# AugmentedStethoscope_vFinal.net
KiCad netlist of a schematic drawn in EAGLE
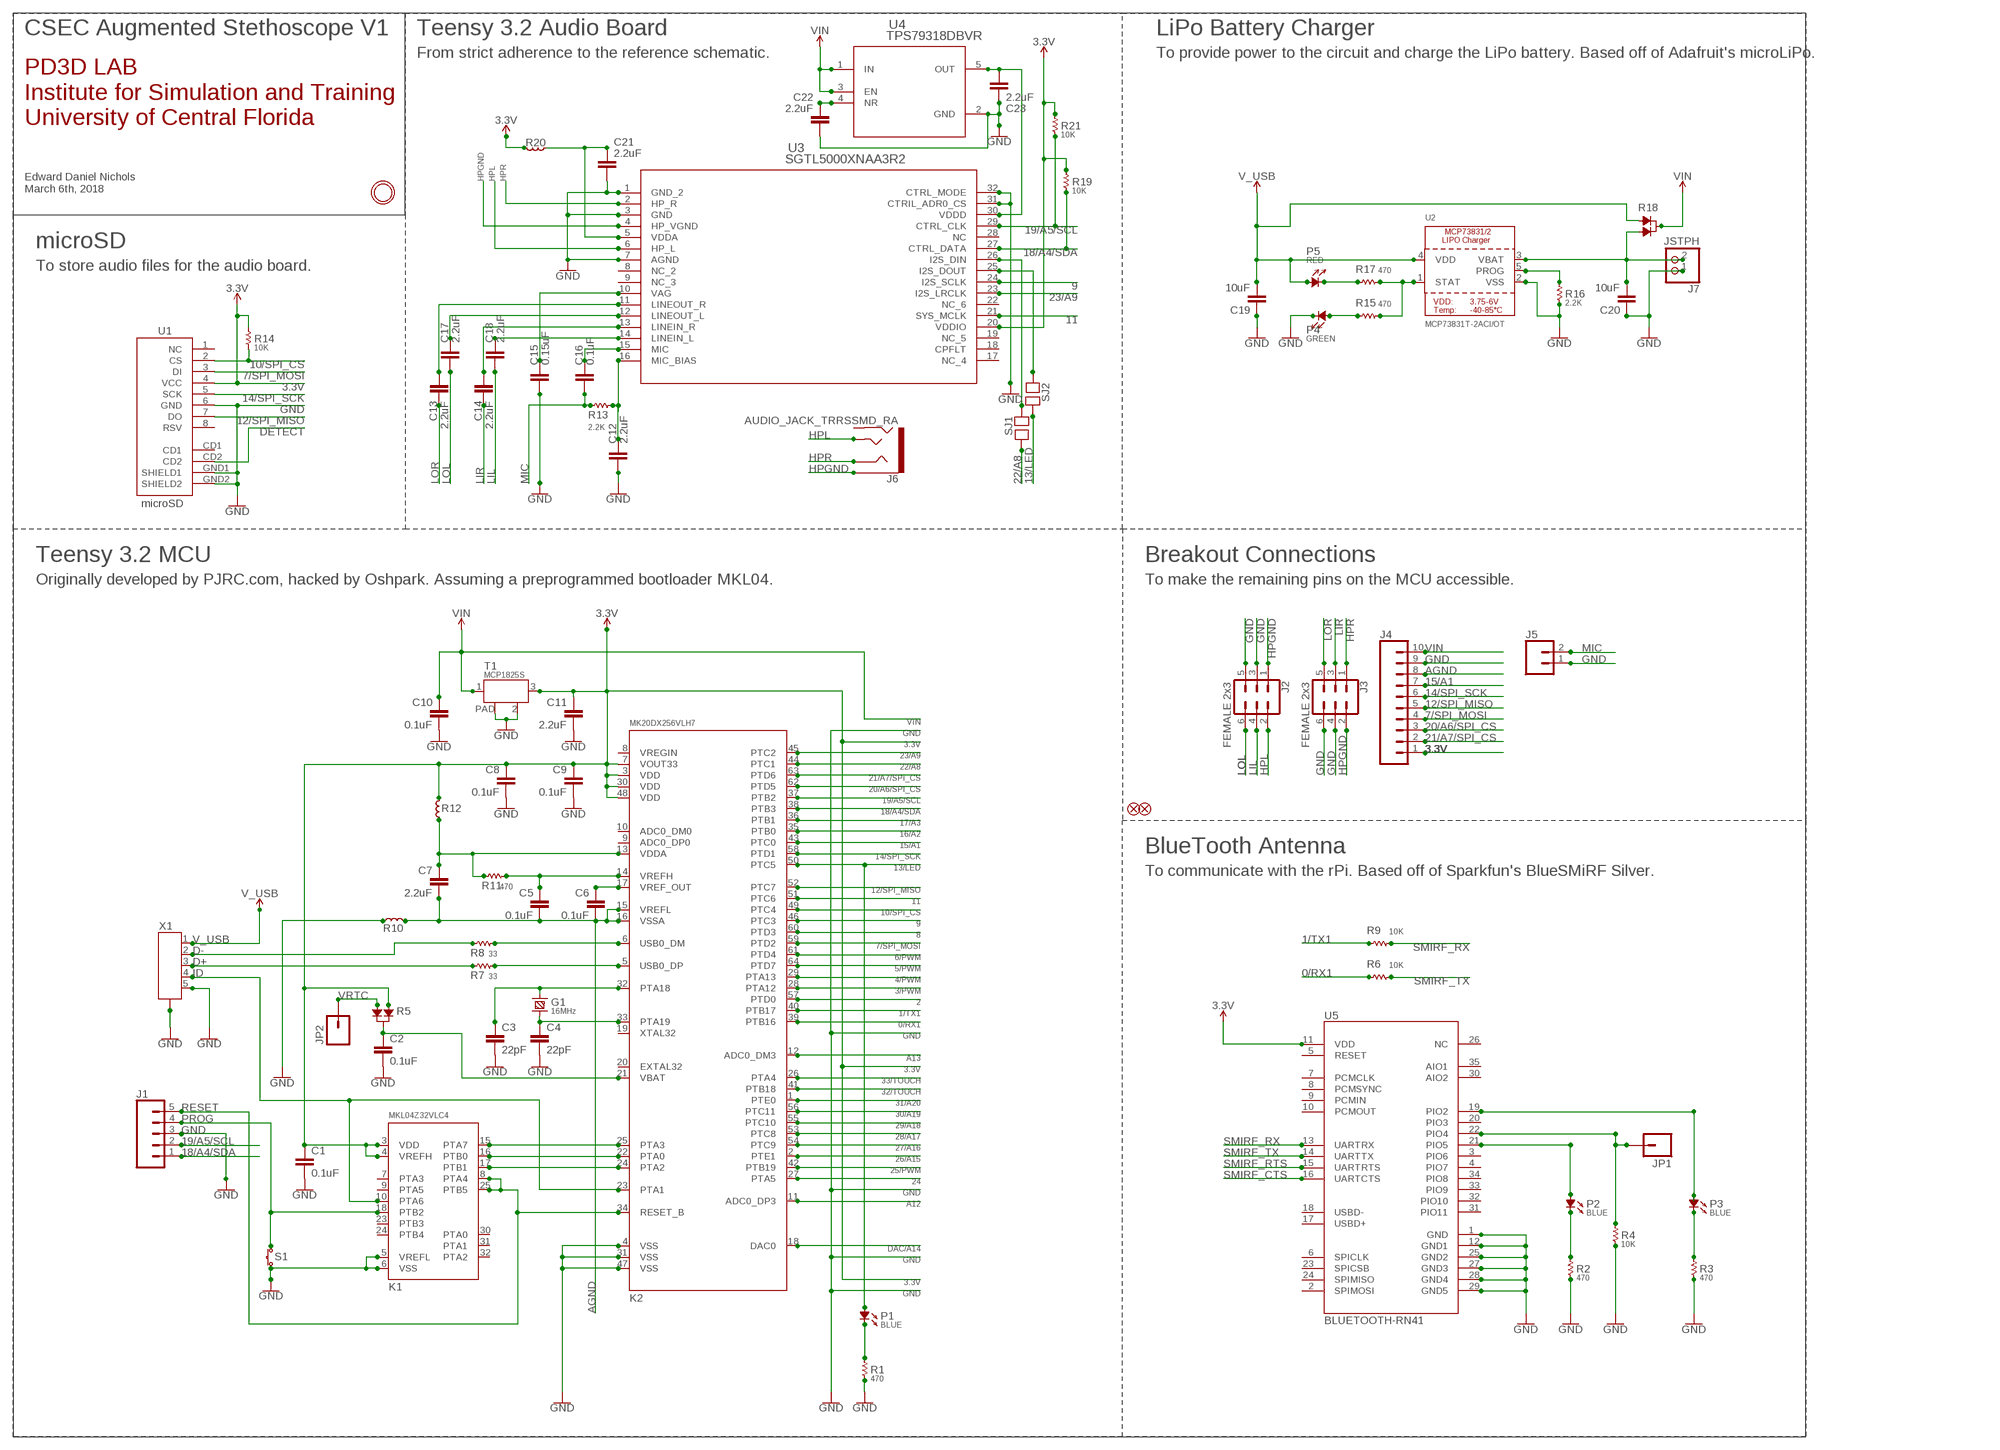
[diagram p0: schematic, sheet 1]

(export (version "E")
  (design (tool "Eeschema 10.0.6"))
  (components
    (comp (ref "C1")
      (value "0.1uF")
      (footprint "eagle-import:0603")
      (libsource (lib "eagle-import") (part "0.1UF-0603-25V-5%"))
    )
    (comp (ref "C2")
      (value "0.1uF")
      (footprint "eagle-import:0603")
      (libsource (lib "eagle-import") (part "0.1UF-0603-25V-5%"))
    )
    (comp (ref "C3")
      (value "22pF")
      (footprint "eagle-import:0603")
      (libsource (lib "eagle-import") (part "22PF-0603-50V-5%"))
    )
    (comp (ref "C4")
      (value "22pF")
      (footprint "eagle-import:0603")
      (libsource (lib "eagle-import") (part "22PF-0603-50V-5%"))
    )
    (comp (ref "C5")
      (value "0.1uF")
      (footprint "eagle-import:0603")
      (libsource (lib "eagle-import") (part "0.1UF-0603-25V-5%"))
    )
    (comp (ref "C6")
      (value "0.1uF")
      (footprint "eagle-import:0603")
      (libsource (lib "eagle-import") (part "0.1UF-0603-25V-5%"))
    )
    (comp (ref "C7")
      (value "2.2uF")
      (footprint "eagle-import:0603")
      (libsource (lib "eagle-import") (part "2.2UF-0603-10V-20%"))
    )
    (comp (ref "C8")
      (value "0.1uF")
      (footprint "eagle-import:0603")
      (libsource (lib "eagle-import") (part "0.1UF-0603-25V-5%"))
    )
    (comp (ref "C9")
      (value "0.1uF")
      (footprint "eagle-import:0603")
      (libsource (lib "eagle-import") (part "0.1UF-0603-25V-5%"))
    )
    (comp (ref "C10")
      (value "0.1uF")
      (footprint "eagle-import:0603")
      (libsource (lib "eagle-import") (part "0.1UF-0603-25V-5%"))
    )
    (comp (ref "C11")
      (value "2.2uF")
      (footprint "eagle-import:0603")
      (libsource (lib "eagle-import") (part "2.2UF-0603-10V-20%"))
    )
    (comp (ref "C12")
      (value "2.2uF")
      (footprint "eagle-import:0603")
      (libsource (lib "eagle-import") (part "2.2UF-0603-10V-20%"))
    )
    (comp (ref "C13")
      (value "2.2uF")
      (footprint "eagle-import:0603")
      (libsource (lib "eagle-import") (part "2.2UF-0603-10V-20%"))
    )
    (comp (ref "C14")
      (value "2.2uF")
      (footprint "eagle-import:0603")
      (libsource (lib "eagle-import") (part "2.2UF-0603-10V-20%"))
    )
    (comp (ref "C15")
      (value "0.15uF")
      (footprint "eagle-import:0603")
      (libsource (lib "eagle-import") (part "0.1UF-0603-25V-5%"))
    )
    (comp (ref "C16")
      (value "0.1uF")
      (footprint "eagle-import:0603")
      (libsource (lib "eagle-import") (part "0.1UF-0603-25V-5%"))
    )
    (comp (ref "C17")
      (value "2.2uF")
      (footprint "eagle-import:0603")
      (libsource (lib "eagle-import") (part "2.2UF-0603-10V-20%"))
    )
    (comp (ref "C18")
      (value "2.2uF")
      (footprint "eagle-import:0603")
      (libsource (lib "eagle-import") (part "2.2UF-0603-10V-20%"))
    )
    (comp (ref "C19")
      (value "10uF")
      (footprint "eagle-import:0805")
      (libsource (lib "eagle-import") (part "10UF-0805-10V-10%"))
    )
    (comp (ref "C20")
      (value "10uF")
      (footprint "eagle-import:0805")
      (libsource (lib "eagle-import") (part "10UF-0805-10V-10%"))
    )
    (comp (ref "C21")
      (value "2.2uF")
      (footprint "eagle-import:0603")
      (libsource (lib "eagle-import") (part "2.2UF-0603-10V-20%"))
    )
    (comp (ref "C22")
      (value "2.2uF")
      (footprint "eagle-import:0603")
      (libsource (lib "eagle-import") (part "2.2UF-0603-10V-20%"))
    )
    (comp (ref "C23")
      (value "2.2uF")
      (footprint "eagle-import:0603")
      (libsource (lib "eagle-import") (part "2.2UF-0603-10V-20%"))
    )
    (comp (ref "FID1")
      (value "FIDUCIAL\"\"")
      (footprint "eagle-import:FIDUCIAL_1MM")
      (fields (field (name "BOM") "EXCLUDE"))
      (libsource (lib "eagle-import") (part "FIDUCIAL{dblquote}{dblquote}"))
    )
    (comp (ref "FID2")
      (value "FIDUCIAL\"\"")
      (footprint "eagle-import:FIDUCIAL_1MM")
      (libsource (lib "eagle-import") (part "FIDUCIAL{dblquote}{dblquote}"))
    )
    (comp (ref "G1")
      (value "16MHz")
      (footprint "eagle-import:HC49US")
      (fields (field (name "MF") "ABRACON") (field (name "MPN") "ABL-16.000MHz-B1U"))
      (libsource (lib "eagle-import") (part "CRYSTAL-HC49US"))
    )
    (comp (ref "J1")
      (value "CONN_05")
      (footprint "eagle-import:1X05")
      (libsource (lib "eagle-import") (part "CONN_05"))
    )
    (comp (ref "J2")
      (value "FEMALE 2x3")
      (footprint "eagle-import:2X3")
      (libsource (lib "eagle-import") (part "CONN_03X2FEMALE"))
    )
    (comp (ref "J3")
      (value "FEMALE 2x3")
      (footprint "eagle-import:2X3")
      (libsource (lib "eagle-import") (part "CONN_03X2FEMALE"))
    )
    (comp (ref "J4")
      (value "CONN_10\"")
      (footprint "eagle-import:1X10")
      (libsource (lib "eagle-import") (part "CONN_10{dblquote}"))
    )
    (comp (ref "J5")
      (value "CONN_02")
      (footprint "eagle-import:1X02")
      (libsource (lib "eagle-import") (part "CONN_02"))
    )
    (comp (ref "J6")
      (value "AUDIO_JACK_TRRSSMD_RA")
      (footprint "eagle-import:AUDIO_JACK_3.5MM_TRRS_SMD_RA")
      (libsource (lib "eagle-import") (part "AUDIO_JACK_TRRSSMD_RA"))
    )
    (comp (ref "J7")
      (value "JSTPH")
      (footprint "eagle-import:JSTPH2")
      (libsource (lib "eagle-import") (part "JST_2PIN"))
    )
    (comp (ref "JP1")
      (value "M01SMDNS")
      (footprint "eagle-import:1X01NS")
      (libsource (lib "eagle-import") (part "M01SMDNS"))
    )
    (comp (ref "JP2")
      (value "M01SMDNS")
      (footprint "eagle-import:1X01NS")
      (libsource (lib "eagle-import") (part "M01SMDNS"))
    )
    (comp (ref "K1")
      (value "MKL04Z32VLC4")
      (footprint "eagle-import:LQFP32-08")
      (fields (field (name "MF") "PJRC") (field (name "MPN") "IC_MKL04Z32_TQFP32"))
      (libsource (lib "eagle-import") (part "MKL04Z32VLC4"))
    )
    (comp (ref "K2")
      (value "MK20DX256VLH7")
      (footprint "eagle-import:LQFP64-05")
      (fields (field (name "MF") "NXP"))
      (libsource (lib "eagle-import") (part "MK20DX256VLH7"))
    )
    (comp (ref "P1")
      (value "BLUE")
      (footprint "eagle-import:LED-0805")
      (fields (field (name "MF") "ROHM Semiconductor") (field (name "MPN") "SML-211DTT86"))
      (libsource (lib "eagle-import") (part "LED"))
    )
    (comp (ref "P2")
      (value "BLUE")
      (footprint "eagle-import:LED-0805")
      (fields (field (name "MF") "ROHM Semiconductor") (field (name "MPN") "SML-211DTT86"))
      (libsource (lib "eagle-import") (part "LED"))
    )
    (comp (ref "P3")
      (value "BLUE")
      (footprint "eagle-import:LED-0805")
      (fields (field (name "MF") "ROHM Semiconductor") (field (name "MPN") "SML-211DTT86"))
      (libsource (lib "eagle-import") (part "LED"))
    )
    (comp (ref "P4")
      (value "GREEN")
      (footprint "eagle-import:LED-0805")
      (fields (field (name "MF") "ROHM Semiconductor") (field (name "MPN") "SML-211DTT86"))
      (libsource (lib "eagle-import") (part "LED"))
    )
    (comp (ref "P5")
      (value "RED")
      (footprint "eagle-import:LED-0805")
      (fields (field (name "MF") "ROHM Semiconductor") (field (name "MPN") "SML-211DTT86"))
      (libsource (lib "eagle-import") (part "LED"))
    )
    (comp (ref "R1")
      (value "470")
      (footprint "eagle-import:R0603")
      (fields (field (name "MF") "Vishay") (field (name "MPN") "CRCW0603470RFKEA"))
      (libsource (lib "eagle-import") (part "RESISTOR-470R"))
    )
    (comp (ref "R2")
      (value "470")
      (footprint "eagle-import:R0603")
      (fields (field (name "MF") "Vishay") (field (name "MPN") "CRCW0603470RFKEA"))
      (libsource (lib "eagle-import") (part "RESISTOR-470R"))
    )
    (comp (ref "R3")
      (value "470")
      (footprint "eagle-import:R0603")
      (fields (field (name "MF") "Vishay") (field (name "MPN") "CRCW0603470RFKEA"))
      (libsource (lib "eagle-import") (part "RESISTOR-470R"))
    )
    (comp (ref "R4")
      (value "10K")
      (footprint "eagle-import:R0603")
      (fields (field (name "MF") "Vishay") (field (name "MPN") "CRCW0603470RFKEA"))
      (libsource (lib "eagle-import") (part "RESISTOR-470R"))
    )
    (comp (ref "R5")
      (value "DIODE_DUAL")
      (footprint "eagle-import:SOT-23")
      (fields (field (name "MF") "NXP Semiconductors") (field (name "MPN") "BAT54C,215"))
      (libsource (lib "eagle-import") (part "DIODE_DUAL"))
    )
    (comp (ref "R6")
      (value "10K")
      (footprint "eagle-import:R0603")
      (fields (field (name "MF") "Panasonic") (field (name "MPN") "ERJ-PA3F33R0V"))
      (libsource (lib "eagle-import") (part "RESISTOR-33R"))
    )
    (comp (ref "R7")
      (value "33")
      (footprint "eagle-import:R0603")
      (fields (field (name "MF") "Panasonic") (field (name "MPN") "ERJ-PA3F33R0V"))
      (libsource (lib "eagle-import") (part "RESISTOR-33R"))
    )
    (comp (ref "R8")
      (value "33")
      (footprint "eagle-import:R0603")
      (fields (field (name "MF") "Panasonic") (field (name "MPN") "ERJ-PA3F33R0V"))
      (libsource (lib "eagle-import") (part "RESISTOR-33R"))
    )
    (comp (ref "R9")
      (value "10K")
      (footprint "eagle-import:R0603")
      (fields (field (name "MF") "Panasonic") (field (name "MPN") "ERJ-PA3F33R0V"))
      (libsource (lib "eagle-import") (part "RESISTOR-33R"))
    )
    (comp (ref "R10")
      (value "FERRITE")
      (footprint "eagle-import:L0603")
      (fields (field (name "MF") "Murata Electronics") (field (name "MPN") " BLM18AG601SN1D"))
      (libsource (lib "eagle-import") (part "FERRITE"))
    )
    (comp (ref "R11")
      (value "470")
      (footprint "eagle-import:R0603")
      (fields (field (name "MF") "Vishay") (field (name "MPN") "CRCW0603470RFKEA"))
      (libsource (lib "eagle-import") (part "RESISTOR-470R"))
    )
    (comp (ref "R12")
      (value "FERRITE")
      (footprint "eagle-import:L0603")
      (fields (field (name "MF") "Murata Electronics") (field (name "MPN") " BLM18AG601SN1D"))
      (libsource (lib "eagle-import") (part "FERRITE"))
    )
    (comp (ref "R13")
      (value "2.2K")
      (footprint "eagle-import:R0603")
      (fields (field (name "MF") "Vishay") (field (name "MPN") "CRCW0603470RFKEA"))
      (libsource (lib "eagle-import") (part "RESISTOR-470R"))
    )
    (comp (ref "R14")
      (value "10K")
      (footprint "eagle-import:R0603")
      (fields (field (name "MF") "Vishay") (field (name "MPN") "CRCW0603470RFKEA"))
      (libsource (lib "eagle-import") (part "RESISTOR-470R"))
    )
    (comp (ref "R15")
      (value "470")
      (footprint "eagle-import:R0603")
      (fields (field (name "MF") "Panasonic") (field (name "MPN") "ERJ-PA3F33R0V"))
      (libsource (lib "eagle-import") (part "RESISTOR-33R"))
    )
    (comp (ref "R16")
      (value "2.2K")
      (footprint "eagle-import:R0603")
      (fields (field (name "MF") "Vishay") (field (name "MPN") "CRCW0603470RFKEA"))
      (libsource (lib "eagle-import") (part "RESISTOR-470R"))
    )
    (comp (ref "R17")
      (value "470")
      (footprint "eagle-import:R0603")
      (fields (field (name "MF") "Panasonic") (field (name "MPN") "ERJ-PA3F33R0V"))
      (libsource (lib "eagle-import") (part "RESISTOR-33R"))
    )
    (comp (ref "R18")
      (value "DIODE_DUAL")
      (footprint "eagle-import:SOT-23")
      (fields (field (name "MF") "NXP Semiconductors") (field (name "MPN") "BAT54C,215"))
      (libsource (lib "eagle-import") (part "DIODE_DUAL"))
    )
    (comp (ref "R19")
      (value "10K")
      (footprint "eagle-import:R0603")
      (fields (field (name "MF") "Vishay") (field (name "MPN") "CRCW0603470RFKEA"))
      (libsource (lib "eagle-import") (part "RESISTOR-470R"))
    )
    (comp (ref "R20")
      (value "FERRITE")
      (footprint "eagle-import:L0603")
      (fields (field (name "MF") "Murata Electronics") (field (name "MPN") " BLM18AG601SN1D"))
      (libsource (lib "eagle-import") (part "FERRITE"))
    )
    (comp (ref "R21")
      (value "10K")
      (footprint "eagle-import:R0603")
      (fields (field (name "MF") "Vishay") (field (name "MPN") "CRCW0603470RFKEA"))
      (libsource (lib "eagle-import") (part "RESISTOR-470R"))
    )
    (comp (ref "S1")
      (value "TACT_SWITCH")
      (footprint "eagle-import:ALPS_SKHH")
      (fields (field (name "MF") "ALPS") (field (name "MPN") "SKHHPKA010"))
      (libsource (lib "eagle-import") (part "TACT_SWITCH"))
    )
    (comp (ref "SJ1")
      (value "SOLDERJUMPER")
      (footprint "eagle-import:SOLDERJUMPER")
      (libsource (lib "eagle-import") (part "SOLDERJUMPER"))
    )
    (comp (ref "SJ2")
      (value "SOLDERJUMPER")
      (footprint "eagle-import:SOLDERJUMPER")
      (libsource (lib "eagle-import") (part "SOLDERJUMPER"))
    )
    (comp (ref "T1")
      (value "MCP1825S")
      (footprint "eagle-import:SOT-223")
      (fields (field (name "MF") "Microchip Technology") (field (name "MPN") "MCP1825S-3302E/DB"))
      (libsource (lib "eagle-import") (part "LDO"))
    )
    (comp (ref "U$1")
      (value "MOUNTINGHOLE2.5")
      (footprint "eagle-import:MOUNTINGHOLE_2.5_PLATED")
      (libsource (lib "eagle-import") (part "MOUNTINGHOLE2.5"))
    )
    (comp (ref "U1")
      (value "microSD")
      (footprint "eagle-import:MICRO-SD-SOCKET-PP")
      (libsource (lib "eagle-import") (part "USD-SOCKETSMD"))
    )
    (comp (ref "U2")
      (value "MCP73831T-2ACI/OT")
      (footprint "eagle-import:SOT23-5")
      (libsource (lib "eagle-import") (part "MCP73831/2"))
    )
    (comp (ref "U3")
      (value "SGTL5000XNAA3R2")
      (footprint "eagle-import:QFN32")
      (libsource (lib "eagle-import") (part "SGTL5000XNAA3R2"))
    )
    (comp (ref "U4")
      (value "TPS79318DBVR")
      (footprint "eagle-import:DBV5")
      (libsource (lib "eagle-import") (part "TPS79318DBVR"))
    )
    (comp (ref "U5")
      (value "BLUETOOTH-RN41")
      (footprint "eagle-import:RN41")
      (libsource (lib "eagle-import") (part "BLUETOOTH-RN41{dblquote}"))
    )
    (comp (ref "X1")
      (value "MINI-USB")
      (footprint "eagle-import:MOLEX_SD-67503-010")
      (fields (field (name "MF") "MOLEX") (field (name "MPN") "0675031020"))
      (libsource (lib "eagle-import") (part "MINI-USBMOLEX_0675031230"))
    )
  )
  (nets
    (net (code "1") (name "/0{slash}RX1") (class "Default")
      (node (ref "K2") (pin "39") (pinfunction "PTB16_39") (pintype "bidirectional"))
      (node (ref "R6") (pin "1") (pinfunction "1_1") (pintype "passive"))
    )
    (net (code "2") (name "/1{slash}TX1") (class "Default")
      (node (ref "K2") (pin "40") (pinfunction "PTB17_40") (pintype "bidirectional"))
      (node (ref "R9") (pin "1") (pinfunction "1_1") (pintype "passive"))
    )
    (net (code "3") (name "/2") (class "Default")
      (node (ref "K2") (pin "57") (pinfunction "PTD0_57") (pintype "bidirectional"))
    )
    (net (code "4") (name "/3{slash}PWM") (class "Default")
      (node (ref "K2") (pin "28") (pinfunction "PTA12_28") (pintype "bidirectional"))
    )
    (net (code "5") (name "/4{slash}PWM") (class "Default")
      (node (ref "K2") (pin "29") (pinfunction "PTA13_29") (pintype "bidirectional"))
    )
    (net (code "6") (name "/5{slash}PWM") (class "Default")
      (node (ref "K2") (pin "64") (pinfunction "PTD7_64") (pintype "bidirectional"))
    )
    (net (code "7") (name "/6{slash}PWM") (class "Default")
      (node (ref "K2") (pin "61") (pinfunction "PTD4_61") (pintype "bidirectional"))
    )
    (net (code "8") (name "/7{slash}SPI_MOSI") (class "Default")
      (node (ref "J4") (pin "4") (pinfunction "4_4") (pintype "passive"))
      (node (ref "K2") (pin "59") (pinfunction "PTD2_59") (pintype "bidirectional"))
      (node (ref "U1") (pin "3") (pinfunction "DI_3") (pintype "bidirectional"))
    )
    (net (code "9") (name "/8") (class "Default")
      (node (ref "K2") (pin "60") (pinfunction "PTD3_60") (pintype "bidirectional"))
    )
    (net (code "10") (name "/9") (class "Default")
      (node (ref "K2") (pin "46") (pinfunction "PTC3_46") (pintype "bidirectional"))
      (node (ref "U3") (pin "24") (pinfunction "I2S_SCLK_24") (pintype "passive"))
    )
    (net (code "11") (name "/10{slash}SPI_CS") (class "Default")
      (node (ref "K2") (pin "49") (pinfunction "PTC4_49") (pintype "bidirectional"))
      (node (ref "R14") (pin "1") (pinfunction "1_1") (pintype "passive"))
      (node (ref "U1") (pin "2") (pinfunction "CS_2") (pintype "bidirectional"))
    )
    (net (code "12") (name "/11") (class "Default")
      (node (ref "K2") (pin "51") (pinfunction "PTC6_51") (pintype "bidirectional"))
      (node (ref "U3") (pin "21") (pinfunction "SYS_MCLK_21") (pintype "passive"))
    )
    (net (code "13") (name "/12{slash}SPI_MISO") (class "Default")
      (node (ref "J4") (pin "5") (pinfunction "5_5") (pintype "passive"))
      (node (ref "K2") (pin "52") (pinfunction "PTC7_52") (pintype "bidirectional"))
      (node (ref "U1") (pin "7") (pinfunction "DO_7") (pintype "bidirectional"))
    )
    (net (code "14") (name "/13{slash}LED") (class "Default")
      (node (ref "K2") (pin "50") (pinfunction "PTC5_50") (pintype "bidirectional"))
      (node (ref "P1") (pin "+") (pinfunction "+_+") (pintype "passive"))
      (node (ref "SJ2") (pin "2") (pinfunction "2_2") (pintype "passive"))
    )
    (net (code "15") (name "/14{slash}SPI_SCK") (class "Default")
      (node (ref "J4") (pin "6") (pinfunction "6_6") (pintype "passive"))
      (node (ref "K2") (pin "58") (pinfunction "PTD1_58") (pintype "bidirectional"))
      (node (ref "U1") (pin "5") (pinfunction "SCK_5") (pintype "bidirectional"))
    )
    (net (code "16") (name "/15{slash}A1") (class "Default")
      (node (ref "J4") (pin "7") (pinfunction "7_7") (pintype "passive"))
      (node (ref "K2") (pin "43") (pinfunction "PTC0_43") (pintype "bidirectional"))
    )
    (net (code "17") (name "/16{slash}A2") (class "Default")
      (node (ref "K2") (pin "35") (pinfunction "PTB0_35") (pintype "bidirectional"))
    )
    (net (code "18") (name "/17{slash}A3") (class "Default")
      (node (ref "K2") (pin "36") (pinfunction "PTB1_36") (pintype "bidirectional"))
    )
    (net (code "19") (name "/18{slash}A4{slash}SDA") (class "Default")
      (node (ref "J1") (pin "1") (pinfunction "1_1") (pintype "passive"))
      (node (ref "K2") (pin "38") (pinfunction "PTB3_38") (pintype "bidirectional"))
      (node (ref "R19") (pin "1") (pinfunction "1_1") (pintype "passive"))
      (node (ref "U3") (pin "27") (pinfunction "CTRL_DATA_27") (pintype "passive"))
    )
    (net (code "20") (name "/19{slash}A5{slash}SCL") (class "Default")
      (node (ref "J1") (pin "2") (pinfunction "2_2") (pintype "passive"))
      (node (ref "K2") (pin "37") (pinfunction "PTB2_37") (pintype "bidirectional"))
      (node (ref "R21") (pin "1") (pinfunction "1_1") (pintype "passive"))
      (node (ref "U3") (pin "29") (pinfunction "CTRL_CLK_29") (pintype "passive"))
    )
    (net (code "21") (name "/20{slash}A6{slash}SPI_CS") (class "Default")
      (node (ref "J4") (pin "3") (pinfunction "3_3") (pintype "passive"))
      (node (ref "K2") (pin "62") (pinfunction "PTD5_62") (pintype "bidirectional"))
    )
    (net (code "22") (name "/21{slash}A7{slash}SPI_CS") (class "Default")
      (node (ref "J4") (pin "2") (pinfunction "2_2") (pintype "passive"))
      (node (ref "K2") (pin "63") (pinfunction "PTD6_63") (pintype "bidirectional"))
    )
    (net (code "23") (name "/22{slash}A8") (class "Default")
      (node (ref "K2") (pin "44") (pinfunction "PTC1_44") (pintype "bidirectional"))
      (node (ref "SJ1") (pin "2") (pinfunction "2_2") (pintype "passive"))
    )
    (net (code "24") (name "/23{slash}A9") (class "Default")
      (node (ref "K2") (pin "45") (pinfunction "PTC2_45") (pintype "bidirectional"))
      (node (ref "U3") (pin "23") (pinfunction "I2S_LRCLK_23") (pintype "passive"))
    )
    (net (code "25") (name "/24") (class "Default")
      (node (ref "K2") (pin "27") (pinfunction "PTA5_27") (pintype "bidirectional"))
    )
    (net (code "26") (name "/25{slash}PWM") (class "Default")
      (node (ref "K2") (pin "42") (pinfunction "PTB19_42") (pintype "bidirectional"))
    )
    (net (code "27") (name "/26{slash}A15") (class "Default")
      (node (ref "K2") (pin "2") (pinfunction "PTE1_2") (pintype "bidirectional"))
    )
    (net (code "28") (name "/27{slash}A16") (class "Default")
      (node (ref "K2") (pin "54") (pinfunction "PTC9_54") (pintype "bidirectional"))
    )
    (net (code "29") (name "/28{slash}A17") (class "Default")
      (node (ref "K2") (pin "53") (pinfunction "PTC8_53") (pintype "bidirectional"))
    )
    (net (code "30") (name "/29{slash}A18") (class "Default")
      (node (ref "K2") (pin "55") (pinfunction "PTC10_55") (pintype "bidirectional"))
    )
    (net (code "31") (name "/30{slash}A19") (class "Default")
      (node (ref "K2") (pin "56") (pinfunction "PTC11_56") (pintype "bidirectional"))
    )
    (net (code "32") (name "/31{slash}A20") (class "Default")
      (node (ref "K2") (pin "1") (pinfunction "PTE0_1") (pintype "bidirectional"))
    )
    (net (code "33") (name "/32{slash}TOUCH") (class "Default")
      (node (ref "K2") (pin "41") (pinfunction "PTB18_41") (pintype "bidirectional"))
    )
    (net (code "34") (name "/33{slash}TOUCH") (class "Default")
      (node (ref "K2") (pin "26") (pinfunction "PTA4_26") (pintype "bidirectional"))
    )
    (net (code "35") (name "/A12") (class "Default")
      (node (ref "K2") (pin "11") (pinfunction "ADC0_DP3_11") (pintype "bidirectional"))
    )
    (net (code "36") (name "/A13") (class "Default")
      (node (ref "K2") (pin "12") (pinfunction "ADC0_DM3_12") (pintype "bidirectional"))
    )
    (net (code "37") (name "/AGND") (class "Default")
      (node (ref "C5") (pin "2") (pinfunction "2_2") (pintype "passive"))
      (node (ref "C6") (pin "2") (pinfunction "2_2") (pintype "passive"))
      (node (ref "C7") (pin "2") (pinfunction "2_2") (pintype "passive"))
      (node (ref "J4") (pin "8") (pinfunction "8_8") (pintype "passive"))
      (node (ref "K2") (pin "15") (pinfunction "VREFL_15") (pintype "bidirectional"))
      (node (ref "K2") (pin "16") (pinfunction "VSSA_16") (pintype "bidirectional"))
      (node (ref "R10") (pin "2") (pinfunction "2_2") (pintype "passive"))
    )
    (net (code "38") (name "/D+") (class "Default")
      (node (ref "R7") (pin "1") (pinfunction "1_1") (pintype "passive"))
      (node (ref "X1") (pin "3") (pinfunction "3_3") (pintype "input"))
    )
    (net (code "39") (name "/D-") (class "Default")
      (node (ref "R8") (pin "1") (pinfunction "1_1") (pintype "passive"))
      (node (ref "X1") (pin "2") (pinfunction "2_2") (pintype "input"))
    )
    (net (code "40") (name "/DAC{slash}A14") (class "Default")
      (node (ref "K2") (pin "18") (pinfunction "DAC0_18") (pintype "bidirectional"))
    )
    (net (code "41") (name "/DETECT") (class "Default")
      (node (ref "U1") (pin "CD2") (pinfunction "CD2_CD2") (pintype "bidirectional"))
    )
    (net (code "42") (name "/HPGND") (class "Default")
      (node (ref "J2") (pin "1") (pinfunction "1_1") (pintype "bidirectional"))
      (node (ref "J3") (pin "2") (pinfunction "2_2") (pintype "bidirectional"))
      (node (ref "J6") (pin "EARTH") (pinfunction "EARTH_EARTH") (pintype "bidirectional"))
      (node (ref "U3") (pin "4") (pinfunction "HP_VGND_4") (pintype "power_in"))
    )
    (net (code "43") (name "/HPL") (class "Default")
      (node (ref "J2") (pin "2") (pinfunction "2_2") (pintype "bidirectional"))
      (node (ref "J6") (pin "TIP") (pinfunction "TIP_TIP") (pintype "bidirectional"))
      (node (ref "U3") (pin "6") (pinfunction "HP_L_6") (pintype "output"))
    )
    (net (code "44") (name "/HPR") (class "Default")
      (node (ref "J3") (pin "1") (pinfunction "1_1") (pintype "bidirectional"))
      (node (ref "J6") (pin "RING1") (pinfunction "RING1_RING1") (pintype "bidirectional"))
      (node (ref "U3") (pin "2") (pinfunction "HP_R_2") (pintype "output"))
    )
    (net (code "45") (name "/ID") (class "Default")
      (node (ref "K1") (pin "10") (pinfunction "PTA6_10") (pintype "bidirectional"))
      (node (ref "K2") (pin "23") (pinfunction "PTA1_23") (pintype "bidirectional"))
      (node (ref "X1") (pin "4") (pinfunction "4_4") (pintype "input"))
    )
    (net (code "46") (name "/LIL") (class "Default")
      (node (ref "C18") (pin "2") (pinfunction "2_2") (pintype "passive"))
      (node (ref "J2") (pin "4") (pinfunction "4_4") (pintype "bidirectional"))
    )
    (net (code "47") (name "/LIR") (class "Default")
      (node (ref "C14") (pin "2") (pinfunction "2_2") (pintype "passive"))
      (node (ref "J3") (pin "3") (pinfunction "3_3") (pintype "bidirectional"))
    )
    (net (code "48") (name "/LOL") (class "Default")
      (node (ref "C17") (pin "2") (pinfunction "2_2") (pintype "passive"))
      (node (ref "J2") (pin "6") (pinfunction "6_6") (pintype "bidirectional"))
    )
    (net (code "49") (name "/LOR") (class "Default")
      (node (ref "C13") (pin "2") (pinfunction "2_2") (pintype "passive"))
      (node (ref "J3") (pin "5") (pinfunction "5_5") (pintype "bidirectional"))
    )
    (net (code "50") (name "/MIC") (class "Default")
      (node (ref "C16") (pin "1") (pinfunction "1_1") (pintype "passive"))
      (node (ref "J5") (pin "2") (pinfunction "2_2") (pintype "passive"))
      (node (ref "R13") (pin "1") (pinfunction "1_1") (pintype "passive"))
    )
    (net (code "51") (name "/PROG") (class "Default")
      (node (ref "J1") (pin "4") (pinfunction "4_4") (pintype "passive"))
      (node (ref "K1") (pin "18") (pinfunction "PTB2_18") (pintype "bidirectional"))
      (node (ref "S1") (pin "1") (pinfunction "1_1") (pintype "passive"))
      (node (ref "S1") (pin "2") (pinfunction "1_2") (pintype "passive"))
    )
    (net (code "52") (name "/RESET") (class "Default")
      (node (ref "J1") (pin "5") (pinfunction "5_5") (pintype "passive"))
      (node (ref "K1") (pin "25") (pinfunction "PTB5_25") (pintype "bidirectional"))
      (node (ref "K1") (pin "8") (pinfunction "PTA4_8") (pintype "bidirectional"))
      (node (ref "K2") (pin "34") (pinfunction "RESET_B_34") (pintype "bidirectional"))
    )
    (net (code "53") (name "/SMIRF_CTS") (class "Default")
      (node (ref "U5") (pin "16") (pinfunction "UARTCTS_16") (pintype "bidirectional"))
    )
    (net (code "54") (name "/SMIRF_RTS") (class "Default")
      (node (ref "U5") (pin "15") (pinfunction "UARTRTS_15") (pintype "bidirectional"))
    )
    (net (code "55") (name "/SMIRF_RX") (class "Default")
      (node (ref "R9") (pin "2") (pinfunction "2_2") (pintype "passive"))
      (node (ref "U5") (pin "13") (pinfunction "UARTRX_13") (pintype "bidirectional"))
    )
    (net (code "56") (name "/SMIRF_TX") (class "Default")
      (node (ref "R6") (pin "2") (pinfunction "2_2") (pintype "passive"))
      (node (ref "U5") (pin "14") (pinfunction "UARTTX_14") (pintype "bidirectional"))
    )
    (net (code "57") (name "/VRTC") (class "Default")
      (node (ref "JP2") (pin "1") (pinfunction "1_1") (pintype "passive"))
      (node (ref "R5") (pin "2") (pinfunction "2_2") (pintype "bidirectional"))
    )
    (net (code "58") (name "3.3V") (class "Default")
      (node (ref "C1") (pin "1") (pinfunction "1_1") (pintype "passive"))
      (node (ref "C11") (pin "1") (pinfunction "1_1") (pintype "passive"))
      (node (ref "C8") (pin "1") (pinfunction "1_1") (pintype "passive"))
      (node (ref "C9") (pin "1") (pinfunction "1_1") (pintype "passive"))
      (node (ref "J4") (pin "1") (pinfunction "1_1") (pintype "passive"))
      (node (ref "K1") (pin "3") (pinfunction "VDD_3") (pintype "bidirectional"))
      (node (ref "K1") (pin "4") (pinfunction "VREFH_4") (pintype "bidirectional"))
      (node (ref "K2") (pin "3") (pinfunction "VDD_3") (pintype "bidirectional"))
      (node (ref "K2") (pin "30") (pinfunction "VDD_30") (pintype "bidirectional"))
      (node (ref "K2") (pin "48") (pinfunction "VDD_48") (pintype "bidirectional"))
      (node (ref "K2") (pin "7") (pinfunction "VOUT33_7") (pintype "bidirectional"))
      (node (ref "R12") (pin "2") (pinfunction "2_2") (pintype "passive"))
      (node (ref "R14") (pin "2") (pinfunction "2_2") (pintype "passive"))
      (node (ref "R19") (pin "2") (pinfunction "2_2") (pintype "passive"))
      (node (ref "R20") (pin "2") (pinfunction "2_2") (pintype "passive"))
      (node (ref "R21") (pin "2") (pinfunction "2_2") (pintype "passive"))
      (node (ref "R5") (pin "1") (pinfunction "1_1") (pintype "bidirectional"))
      (node (ref "T1") (pin "3") (pinfunction "OUT_3") (pintype "bidirectional"))
      (node (ref "U1") (pin "4") (pinfunction "VCC_4") (pintype "bidirectional"))
      (node (ref "U3") (pin "20") (pinfunction "VDDIO_20") (pintype "power_in"))
      (node (ref "U5") (pin "11") (pinfunction "VDD_11") (pintype "bidirectional"))
    )
    (net (code "59") (name "GND") (class "Default")
      (node (ref "C1") (pin "2") (pinfunction "2_2") (pintype "passive"))
      (node (ref "C10") (pin "2") (pinfunction "2_2") (pintype "passive"))
      (node (ref "C11") (pin "2") (pinfunction "2_2") (pintype "passive"))
      (node (ref "C12") (pin "2") (pinfunction "2_2") (pintype "passive"))
      (node (ref "C15") (pin "1") (pinfunction "1_1") (pintype "passive"))
      (node (ref "C19") (pin "1") (pinfunction "1_1") (pintype "passive"))
      (node (ref "C2") (pin "2") (pinfunction "2_2") (pintype "passive"))
      (node (ref "C20") (pin "1") (pinfunction "1_1") (pintype "passive"))
      (node (ref "C21") (pin "2") (pinfunction "2_2") (pintype "passive"))
      (node (ref "C22") (pin "2") (pinfunction "2_2") (pintype "passive"))
      (node (ref "C23") (pin "1") (pinfunction "1_1") (pintype "passive"))
      (node (ref "C3") (pin "2") (pinfunction "2_2") (pintype "passive"))
      (node (ref "C4") (pin "2") (pinfunction "2_2") (pintype "passive"))
      (node (ref "C8") (pin "2") (pinfunction "2_2") (pintype "passive"))
      (node (ref "C9") (pin "2") (pinfunction "2_2") (pintype "passive"))
      (node (ref "J1") (pin "3") (pinfunction "3_3") (pintype "passive"))
      (node (ref "J2") (pin "3") (pinfunction "3_3") (pintype "bidirectional"))
      (node (ref "J2") (pin "5") (pinfunction "5_5") (pintype "bidirectional"))
      (node (ref "J3") (pin "4") (pinfunction "4_4") (pintype "bidirectional"))
      (node (ref "J3") (pin "6") (pinfunction "6_6") (pintype "bidirectional"))
      (node (ref "J4") (pin "9") (pinfunction "9_9") (pintype "passive"))
      (node (ref "J5") (pin "1") (pinfunction "1_1") (pintype "passive"))
      (node (ref "J7") (pin "1") (pinfunction "1_1") (pintype "passive"))
      (node (ref "K1") (pin "5") (pinfunction "VREFL_5") (pintype "bidirectional"))
      (node (ref "K1") (pin "6") (pinfunction "VSS_6") (pintype "bidirectional"))
      (node (ref "K2") (pin "31") (pinfunction "VSS_31") (pintype "bidirectional"))
      (node (ref "K2") (pin "4") (pinfunction "VSS_4") (pintype "bidirectional"))
      (node (ref "K2") (pin "47") (pinfunction "VSS_47") (pintype "bidirectional"))
      (node (ref "P4") (pin "-") (pinfunction "-_-") (pintype "passive"))
      (node (ref "R1") (pin "1") (pinfunction "1_1") (pintype "passive"))
      (node (ref "R10") (pin "1") (pinfunction "1_1") (pintype "passive"))
      (node (ref "R16") (pin "1") (pinfunction "1_1") (pintype "passive"))
      (node (ref "R2") (pin "1") (pinfunction "1_1") (pintype "passive"))
      (node (ref "R3") (pin "1") (pinfunction "1_1") (pintype "passive"))
      (node (ref "R4") (pin "1") (pinfunction "1_1") (pintype "passive"))
      (node (ref "S1") (pin "3") (pinfunction "3_3") (pintype "passive"))
      (node (ref "S1") (pin "4") (pinfunction "3_4") (pintype "passive"))
      (node (ref "T1") (pin "2") (pinfunction "GND_2") (pintype "bidirectional"))
      (node (ref "T1") (pin "PAD") (pinfunction "PAD_PAD") (pintype "bidirectional"))
      (node (ref "U1") (pin "6") (pinfunction "GND_6") (pintype "bidirectional"))
      (node (ref "U1") (pin "GND1") (pinfunction "SHIELD1_GND1") (pintype "bidirectional"))
      (node (ref "U1") (pin "GND2") (pinfunction "SHIELD2_GND2") (pintype "bidirectional"))
      (node (ref "U2") (pin "2") (pinfunction "VSS_2") (pintype "power_in"))
      (node (ref "U3") (pin "1") (pinfunction "GND_2_1") (pintype "power_in"))
      (node (ref "U3") (pin "3") (pinfunction "GND_3") (pintype "power_in"))
      (node (ref "U3") (pin "31") (pinfunction "CTRIL_ADR0_CS_31") (pintype "passive"))
      (node (ref "U3") (pin "32") (pinfunction "CTRL_MODE_32") (pintype "passive"))
      (node (ref "U3") (pin "7") (pinfunction "AGND_7") (pintype "power_in"))
      (node (ref "U4") (pin "2") (pinfunction "GND_2") (pintype "power_in"))
      (node (ref "U5") (pin "1") (pinfunction "GND_1") (pintype "bidirectional"))
      (node (ref "U5") (pin "12") (pinfunction "GND1_12") (pintype "bidirectional"))
      (node (ref "U5") (pin "25") (pinfunction "GND2_25") (pintype "bidirectional"))
      (node (ref "U5") (pin "27") (pinfunction "GND3_27") (pintype "bidirectional"))
      (node (ref "U5") (pin "28") (pinfunction "GND4_28") (pintype "bidirectional"))
      (node (ref "U5") (pin "29") (pinfunction "GND5_29") (pintype "bidirectional"))
      (node (ref "X1") (pin "5") (pinfunction "5_5") (pintype "input"))
      (node (ref "X1") (pin "P$1") (pinfunction "CASE_P$1") (pintype "input"))
      (node (ref "X1") (pin "P$2") (pinfunction "CASE_P$2") (pintype "input"))
      (node (ref "X1") (pin "P$3") (pinfunction "CASE_P$3") (pintype "input"))
      (node (ref "X1") (pin "P$4") (pinfunction "CASE_P$4") (pintype "input"))
      (node (ref "X1") (pin "P$5") (pinfunction "CASE_P$5") (pintype "input"))
      (node (ref "X1") (pin "P$6") (pinfunction "CASE_P$6") (pintype "input"))
    )
    (net (code "60") (name "Net-(K1-PTA7)") (class "Default")
      (node (ref "K1") (pin "15") (pinfunction "PTA7_15") (pintype "bidirectional"))
      (node (ref "K2") (pin "25") (pinfunction "PTA3_25") (pintype "bidirectional"))
    )
    (net (code "61") (name "Net-(K1-PTB0)") (class "Default")
      (node (ref "K1") (pin "16") (pinfunction "PTB0_16") (pintype "bidirectional"))
      (node (ref "K2") (pin "22") (pinfunction "PTA0_22") (pintype "bidirectional"))
    )
    (net (code "62") (name "Net-(K1-PTB1)") (class "Default")
      (node (ref "K1") (pin "17") (pinfunction "PTB1_17") (pintype "bidirectional"))
      (node (ref "K2") (pin "24") (pinfunction "PTA2_24") (pintype "bidirectional"))
    )
    (net (code "63") (name "Net-(K2-PTA18)") (class "Default")
      (node (ref "C3") (pin "1") (pinfunction "1_1") (pintype "passive"))
      (node (ref "G1") (pin "1") (pinfunction "1_1") (pintype "passive"))
      (node (ref "K2") (pin "32") (pinfunction "PTA18_32") (pintype "bidirectional"))
    )
    (net (code "64") (name "Net-(K2-PTA19)") (class "Default")
      (node (ref "C4") (pin "1") (pinfunction "1_1") (pintype "passive"))
      (node (ref "G1") (pin "2") (pinfunction "2_2") (pintype "passive"))
      (node (ref "K2") (pin "33") (pinfunction "PTA19_33") (pintype "bidirectional"))
    )
    (net (code "65") (name "Net-(K2-USB0_DM)") (class "Default")
      (node (ref "K2") (pin "6") (pinfunction "USB0_DM_6") (pintype "bidirectional"))
      (node (ref "R8") (pin "2") (pinfunction "2_2") (pintype "passive"))
    )
    (net (code "66") (name "Net-(K2-USB0_DP)") (class "Default")
      (node (ref "K2") (pin "5") (pinfunction "USB0_DP_5") (pintype "bidirectional"))
      (node (ref "R7") (pin "2") (pinfunction "2_2") (pintype "passive"))
    )
    (net (code "67") (name "Net-(K2-VBAT)") (class "Default")
      (node (ref "C2") (pin "1") (pinfunction "1_1") (pintype "passive"))
      (node (ref "K2") (pin "21") (pinfunction "VBAT_21") (pintype "bidirectional"))
      (node (ref "R5") (pin "3") (pinfunction "3_3") (pintype "bidirectional"))
    )
    (net (code "68") (name "Net-(K2-VDDA)") (class "Default")
      (node (ref "C7") (pin "1") (pinfunction "1_1") (pintype "passive"))
      (node (ref "K2") (pin "13") (pinfunction "VDDA_13") (pintype "bidirectional"))
      (node (ref "R11") (pin "1") (pinfunction "1_1") (pintype "passive"))
      (node (ref "R12") (pin "1") (pinfunction "1_1") (pintype "passive"))
    )
    (net (code "69") (name "Net-(K2-VREFH)") (class "Default")
      (node (ref "C5") (pin "1") (pinfunction "1_1") (pintype "passive"))
      (node (ref "K2") (pin "14") (pinfunction "VREFH_14") (pintype "bidirectional"))
      (node (ref "R11") (pin "2") (pinfunction "2_2") (pintype "passive"))
    )
    (net (code "70") (name "Net-(K2-VREF_OUT)") (class "Default")
      (node (ref "C6") (pin "1") (pinfunction "1_1") (pintype "passive"))
      (node (ref "K2") (pin "17") (pinfunction "VREF_OUT_17") (pintype "bidirectional"))
    )
    (net (code "71") (name "Net-(P1-Pad-)") (class "Default")
      (node (ref "P1") (pin "-") (pinfunction "-_-") (pintype "passive"))
      (node (ref "R1") (pin "2") (pinfunction "2_2") (pintype "passive"))
    )
    (net (code "72") (name "Net-(P2-Pad-)") (class "Default")
      (node (ref "P2") (pin "-") (pinfunction "-_-") (pintype "passive"))
      (node (ref "R2") (pin "2") (pinfunction "2_2") (pintype "passive"))
    )
    (net (code "73") (name "Net-(P3-Pad-)") (class "Default")
      (node (ref "P3") (pin "-") (pinfunction "-_-") (pintype "passive"))
      (node (ref "R3") (pin "2") (pinfunction "2_2") (pintype "passive"))
    )
    (net (code "74") (name "Net-(P4-Pad+)") (class "Default")
      (node (ref "P4") (pin "+") (pinfunction "+_+") (pintype "passive"))
      (node (ref "R15") (pin "1") (pinfunction "1_1") (pintype "passive"))
    )
    (net (code "75") (name "Net-(P5-Pad-)") (class "Default")
      (node (ref "P5") (pin "-") (pinfunction "-_-") (pintype "passive"))
      (node (ref "R17") (pin "1") (pinfunction "1_1") (pintype "passive"))
    )
    (net (code "76") (name "Net-(U2-PROG)") (class "Default")
      (node (ref "R16") (pin "2") (pinfunction "2_2") (pintype "passive"))
      (node (ref "U2") (pin "5") (pinfunction "PROG_5") (pintype "input"))
    )
    (net (code "77") (name "Net-(U2-STAT)") (class "Default")
      (node (ref "R15") (pin "2") (pinfunction "2_2") (pintype "passive"))
      (node (ref "R17") (pin "2") (pinfunction "2_2") (pintype "passive"))
      (node (ref "U2") (pin "1") (pinfunction "STAT_1") (pintype "output"))
    )
    (net (code "78") (name "Net-(U2-VBAT)") (class "Default")
      (node (ref "C20") (pin "2") (pinfunction "2_2") (pintype "passive"))
      (node (ref "J7") (pin "2") (pinfunction "2_2") (pintype "passive"))
      (node (ref "R18") (pin "2") (pinfunction "2_2") (pintype "bidirectional"))
      (node (ref "U2") (pin "3") (pinfunction "VBAT_3") (pintype "power_in"))
    )
    (net (code "79") (name "Net-(U3-I2S_DIN)") (class "Default")
      (node (ref "SJ1") (pin "1") (pinfunction "1_1") (pintype "passive"))
      (node (ref "U3") (pin "26") (pinfunction "I2S_DIN_26") (pintype "input"))
    )
    (net (code "80") (name "Net-(U3-I2S_DOUT)") (class "Default")
      (node (ref "SJ2") (pin "1") (pinfunction "1_1") (pintype "passive"))
      (node (ref "U3") (pin "25") (pinfunction "I2S_DOUT_25") (pintype "output"))
    )
    (net (code "81") (name "Net-(U3-LINEIN_L)") (class "Default")
      (node (ref "C18") (pin "1") (pinfunction "1_1") (pintype "passive"))
      (node (ref "U3") (pin "14") (pinfunction "LINEIN_L_14") (pintype "input"))
    )
    (net (code "82") (name "Net-(U3-LINEIN_R)") (class "Default")
      (node (ref "C14") (pin "1") (pinfunction "1_1") (pintype "passive"))
      (node (ref "U3") (pin "13") (pinfunction "LINEIN_R_13") (pintype "input"))
    )
    (net (code "83") (name "Net-(U3-LINEOUT_L)") (class "Default")
      (node (ref "C17") (pin "1") (pinfunction "1_1") (pintype "passive"))
      (node (ref "U3") (pin "12") (pinfunction "LINEOUT_L_12") (pintype "output"))
    )
    (net (code "84") (name "Net-(U3-LINEOUT_R)") (class "Default")
      (node (ref "C13") (pin "1") (pinfunction "1_1") (pintype "passive"))
      (node (ref "U3") (pin "11") (pinfunction "LINEOUT_R_11") (pintype "output"))
    )
    (net (code "85") (name "Net-(U3-MIC)") (class "Default")
      (node (ref "C16") (pin "2") (pinfunction "2_2") (pintype "passive"))
      (node (ref "U3") (pin "15") (pinfunction "MIC_15") (pintype "input"))
    )
    (net (code "86") (name "Net-(U3-MIC_BIAS)") (class "Default")
      (node (ref "C12") (pin "1") (pinfunction "1_1") (pintype "passive"))
      (node (ref "R13") (pin "2") (pinfunction "2_2") (pintype "passive"))
      (node (ref "U3") (pin "16") (pinfunction "MIC_BIAS_16") (pintype "passive"))
    )
    (net (code "87") (name "Net-(U3-VAG)") (class "Default")
      (node (ref "C15") (pin "2") (pinfunction "2_2") (pintype "passive"))
      (node (ref "U3") (pin "10") (pinfunction "VAG_10") (pintype "passive"))
    )
    (net (code "88") (name "Net-(U3-VDDA)") (class "Default")
      (node (ref "C21") (pin "1") (pinfunction "1_1") (pintype "passive"))
      (node (ref "R20") (pin "1") (pinfunction "1_1") (pintype "passive"))
      (node (ref "U3") (pin "5") (pinfunction "VDDA_5") (pintype "power_in"))
    )
    (net (code "89") (name "Net-(U3-VDDD)") (class "Default")
      (node (ref "C23") (pin "2") (pinfunction "2_2") (pintype "passive"))
      (node (ref "U3") (pin "30") (pinfunction "VDDD_30") (pintype "power_in"))
      (node (ref "U4") (pin "5") (pinfunction "OUT_5") (pintype "output"))
    )
    (net (code "90") (name "Net-(U4-NR)") (class "Default")
      (node (ref "C22") (pin "1") (pinfunction "1_1") (pintype "passive"))
      (node (ref "U4") (pin "4") (pinfunction "NR_4") (pintype "passive"))
    )
    (net (code "91") (name "Net-(U5-PIO2)") (class "Default")
      (node (ref "P3") (pin "+") (pinfunction "+_+") (pintype "passive"))
      (node (ref "U5") (pin "19") (pinfunction "PIO2_19") (pintype "bidirectional"))
    )
    (net (code "92") (name "Net-(U5-PIO4)") (class "Default")
      (node (ref "JP1") (pin "1") (pinfunction "1_1") (pintype "passive"))
      (node (ref "R4") (pin "2") (pinfunction "2_2") (pintype "passive"))
      (node (ref "U5") (pin "22") (pinfunction "PIO4_22") (pintype "bidirectional"))
    )
    (net (code "93") (name "Net-(U5-PIO5)") (class "Default")
      (node (ref "P2") (pin "+") (pinfunction "+_+") (pintype "passive"))
      (node (ref "U5") (pin "21") (pinfunction "PIO5_21") (pintype "bidirectional"))
    )
    (net (code "94") (name "VIN") (class "Default")
      (node (ref "C10") (pin "1") (pinfunction "1_1") (pintype "passive"))
      (node (ref "J4") (pin "10") (pinfunction "10_10") (pintype "passive"))
      (node (ref "R18") (pin "3") (pinfunction "3_3") (pintype "bidirectional"))
      (node (ref "T1") (pin "1") (pinfunction "IN_1") (pintype "bidirectional"))
      (node (ref "U4") (pin "1") (pinfunction "IN_1") (pintype "input"))
      (node (ref "U4") (pin "3") (pinfunction "EN_3") (pintype "passive"))
    )
    (net (code "95") (name "V_USB") (class "Default")
      (node (ref "C19") (pin "2") (pinfunction "2_2") (pintype "passive"))
      (node (ref "P5") (pin "+") (pinfunction "+_+") (pintype "passive"))
      (node (ref "R18") (pin "1") (pinfunction "1_1") (pintype "bidirectional"))
      (node (ref "U2") (pin "4") (pinfunction "VDD_4") (pintype "power_in"))
      (node (ref "X1") (pin "1") (pinfunction "1_1") (pintype "input"))
    )
    (net (code "96") (name "unconnected-(J6-PadRING2)") (class "Default")
      (node (ref "J6") (pin "RING2") (pinfunction "RING2_RING2") (pintype "bidirectional"))
    )
    (net (code "97") (name "unconnected-(K1-PTA0-Pad30)") (class "Default")
      (node (ref "K1") (pin "30") (pinfunction "PTA0_30") (pintype "bidirectional"))
    )
    (net (code "98") (name "unconnected-(K1-PTA1-Pad31)") (class "Default")
      (node (ref "K1") (pin "31") (pinfunction "PTA1_31") (pintype "bidirectional"))
    )
    (net (code "99") (name "unconnected-(K1-PTA2-Pad32)") (class "Default")
      (node (ref "K1") (pin "32") (pinfunction "PTA2_32") (pintype "bidirectional"))
    )
    (net (code "100") (name "unconnected-(K1-PTA3-Pad7)") (class "Default")
      (node (ref "K1") (pin "7") (pinfunction "PTA3_7") (pintype "bidirectional"))
    )
    (net (code "101") (name "unconnected-(K1-PTA5-Pad9)") (class "Default")
      (node (ref "K1") (pin "9") (pinfunction "PTA5_9") (pintype "bidirectional"))
    )
    (net (code "102") (name "unconnected-(K1-PTB3-Pad23)") (class "Default")
      (node (ref "K1") (pin "23") (pinfunction "PTB3_23") (pintype "bidirectional"))
    )
    (net (code "103") (name "unconnected-(K1-PTB4-Pad24)") (class "Default")
      (node (ref "K1") (pin "24") (pinfunction "PTB4_24") (pintype "bidirectional"))
    )
    (net (code "104") (name "unconnected-(K2-ADC0_DM0-Pad10)") (class "Default")
      (node (ref "K2") (pin "10") (pinfunction "ADC0_DM0_10") (pintype "bidirectional"))
    )
    (net (code "105") (name "unconnected-(K2-ADC0_DP0-Pad9)") (class "Default")
      (node (ref "K2") (pin "9") (pinfunction "ADC0_DP0_9") (pintype "bidirectional"))
    )
    (net (code "106") (name "unconnected-(K2-EXTAL32-Pad20)") (class "Default")
      (node (ref "K2") (pin "20") (pinfunction "EXTAL32_20") (pintype "bidirectional"))
    )
    (net (code "107") (name "unconnected-(K2-VREGIN-Pad8)") (class "Default")
      (node (ref "K2") (pin "8") (pinfunction "VREGIN_8") (pintype "bidirectional"))
    )
    (net (code "108") (name "unconnected-(K2-XTAL32-Pad19)") (class "Default")
      (node (ref "K2") (pin "19") (pinfunction "XTAL32_19") (pintype "bidirectional"))
    )
    (net (code "109") (name "unconnected-(U1-NC-Pad1)") (class "Default")
      (node (ref "U1") (pin "1") (pinfunction "NC_1") (pintype "bidirectional"))
    )
    (net (code "110") (name "unconnected-(U1-PadCD1)") (class "Default")
      (node (ref "U1") (pin "CD1") (pinfunction "CD1_CD1") (pintype "bidirectional"))
    )
    (net (code "111") (name "unconnected-(U1-RSV-Pad8)") (class "Default")
      (node (ref "U1") (pin "8") (pinfunction "RSV_8") (pintype "bidirectional"))
    )
    (net (code "112") (name "unconnected-(U3-CPFLT-Pad18)") (class "Default")
      (node (ref "U3") (pin "18") (pinfunction "CPFLT_18") (pintype "passive"))
    )
    (net (code "113") (name "unconnected-(U3-NC-Pad28)") (class "Default")
      (node (ref "U3") (pin "28") (pinfunction "NC_28") (pintype "passive"))
    )
    (net (code "114") (name "unconnected-(U3-NC_2-Pad8)") (class "Default")
      (node (ref "U3") (pin "8") (pinfunction "NC_2_8") (pintype "passive"))
    )
    (net (code "115") (name "unconnected-(U3-NC_3-Pad9)") (class "Default")
      (node (ref "U3") (pin "9") (pinfunction "NC_3_9") (pintype "passive"))
    )
    (net (code "116") (name "unconnected-(U3-NC_4-Pad17)") (class "Default")
      (node (ref "U3") (pin "17") (pinfunction "NC_4_17") (pintype "passive"))
    )
    (net (code "117") (name "unconnected-(U3-NC_5-Pad19)") (class "Default")
      (node (ref "U3") (pin "19") (pinfunction "NC_5_19") (pintype "passive"))
    )
    (net (code "118") (name "unconnected-(U3-NC_6-Pad22)") (class "Default")
      (node (ref "U3") (pin "22") (pinfunction "NC_6_22") (pintype "passive"))
    )
    (net (code "119") (name "unconnected-(U5-AIO1-Pad35)") (class "Default")
      (node (ref "U5") (pin "35") (pinfunction "AIO1_35") (pintype "bidirectional"))
    )
    (net (code "120") (name "unconnected-(U5-AIO2-Pad30)") (class "Default")
      (node (ref "U5") (pin "30") (pinfunction "AIO2_30") (pintype "bidirectional"))
    )
    (net (code "121") (name "unconnected-(U5-NC-Pad26)") (class "Default")
      (node (ref "U5") (pin "26") (pinfunction "NC_26") (pintype "bidirectional"))
    )
    (net (code "122") (name "unconnected-(U5-PCMCLK-Pad7)") (class "Default")
      (node (ref "U5") (pin "7") (pinfunction "PCMCLK_7") (pintype "bidirectional"))
    )
    (net (code "123") (name "unconnected-(U5-PCMIN-Pad9)") (class "Default")
      (node (ref "U5") (pin "9") (pinfunction "PCMIN_9") (pintype "bidirectional"))
    )
    (net (code "124") (name "unconnected-(U5-PCMOUT-Pad10)") (class "Default")
      (node (ref "U5") (pin "10") (pinfunction "PCMOUT_10") (pintype "bidirectional"))
    )
    (net (code "125") (name "unconnected-(U5-PCMSYNC-Pad8)") (class "Default")
      (node (ref "U5") (pin "8") (pinfunction "PCMSYNC_8") (pintype "bidirectional"))
    )
    (net (code "126") (name "unconnected-(U5-PIO3-Pad20)") (class "Default")
      (node (ref "U5") (pin "20") (pinfunction "PIO3_20") (pintype "bidirectional"))
    )
    (net (code "127") (name "unconnected-(U5-PIO6-Pad3)") (class "Default")
      (node (ref "U5") (pin "3") (pinfunction "PIO6_3") (pintype "bidirectional"))
    )
    (net (code "128") (name "unconnected-(U5-PIO7-Pad4)") (class "Default")
      (node (ref "U5") (pin "4") (pinfunction "PIO7_4") (pintype "bidirectional"))
    )
    (net (code "129") (name "unconnected-(U5-PIO8-Pad34)") (class "Default")
      (node (ref "U5") (pin "34") (pinfunction "PIO8_34") (pintype "bidirectional"))
    )
    (net (code "130") (name "unconnected-(U5-PIO9-Pad33)") (class "Default")
      (node (ref "U5") (pin "33") (pinfunction "PIO9_33") (pintype "bidirectional"))
    )
    (net (code "131") (name "unconnected-(U5-PIO10-Pad32)") (class "Default")
      (node (ref "U5") (pin "32") (pinfunction "PIO10_32") (pintype "bidirectional"))
    )
    (net (code "132") (name "unconnected-(U5-PIO11-Pad31)") (class "Default")
      (node (ref "U5") (pin "31") (pinfunction "PIO11_31") (pintype "bidirectional"))
    )
    (net (code "133") (name "unconnected-(U5-RESET-Pad5)") (class "Default")
      (node (ref "U5") (pin "5") (pinfunction "RESET_5") (pintype "bidirectional"))
    )
    (net (code "134") (name "unconnected-(U5-SPICLK-Pad6)") (class "Default")
      (node (ref "U5") (pin "6") (pinfunction "SPICLK_6") (pintype "bidirectional"))
    )
    (net (code "135") (name "unconnected-(U5-SPICSB-Pad23)") (class "Default")
      (node (ref "U5") (pin "23") (pinfunction "SPICSB_23") (pintype "bidirectional"))
    )
    (net (code "136") (name "unconnected-(U5-SPIMISO-Pad24)") (class "Default")
      (node (ref "U5") (pin "24") (pinfunction "SPIMISO_24") (pintype "bidirectional"))
    )
    (net (code "137") (name "unconnected-(U5-SPIMOSI-Pad2)") (class "Default")
      (node (ref "U5") (pin "2") (pinfunction "SPIMOSI_2") (pintype "bidirectional"))
    )
    (net (code "138") (name "unconnected-(U5-USBD+-Pad17)") (class "Default")
      (node (ref "U5") (pin "17") (pinfunction "USBD+_17") (pintype "bidirectional"))
    )
    (net (code "139") (name "unconnected-(U5-USBD--Pad18)") (class "Default")
      (node (ref "U5") (pin "18") (pinfunction "USBD-_18") (pintype "bidirectional"))
    )
  )
)
